# Power.net
KiCad netlist of a schematic drawn in Altium Designer
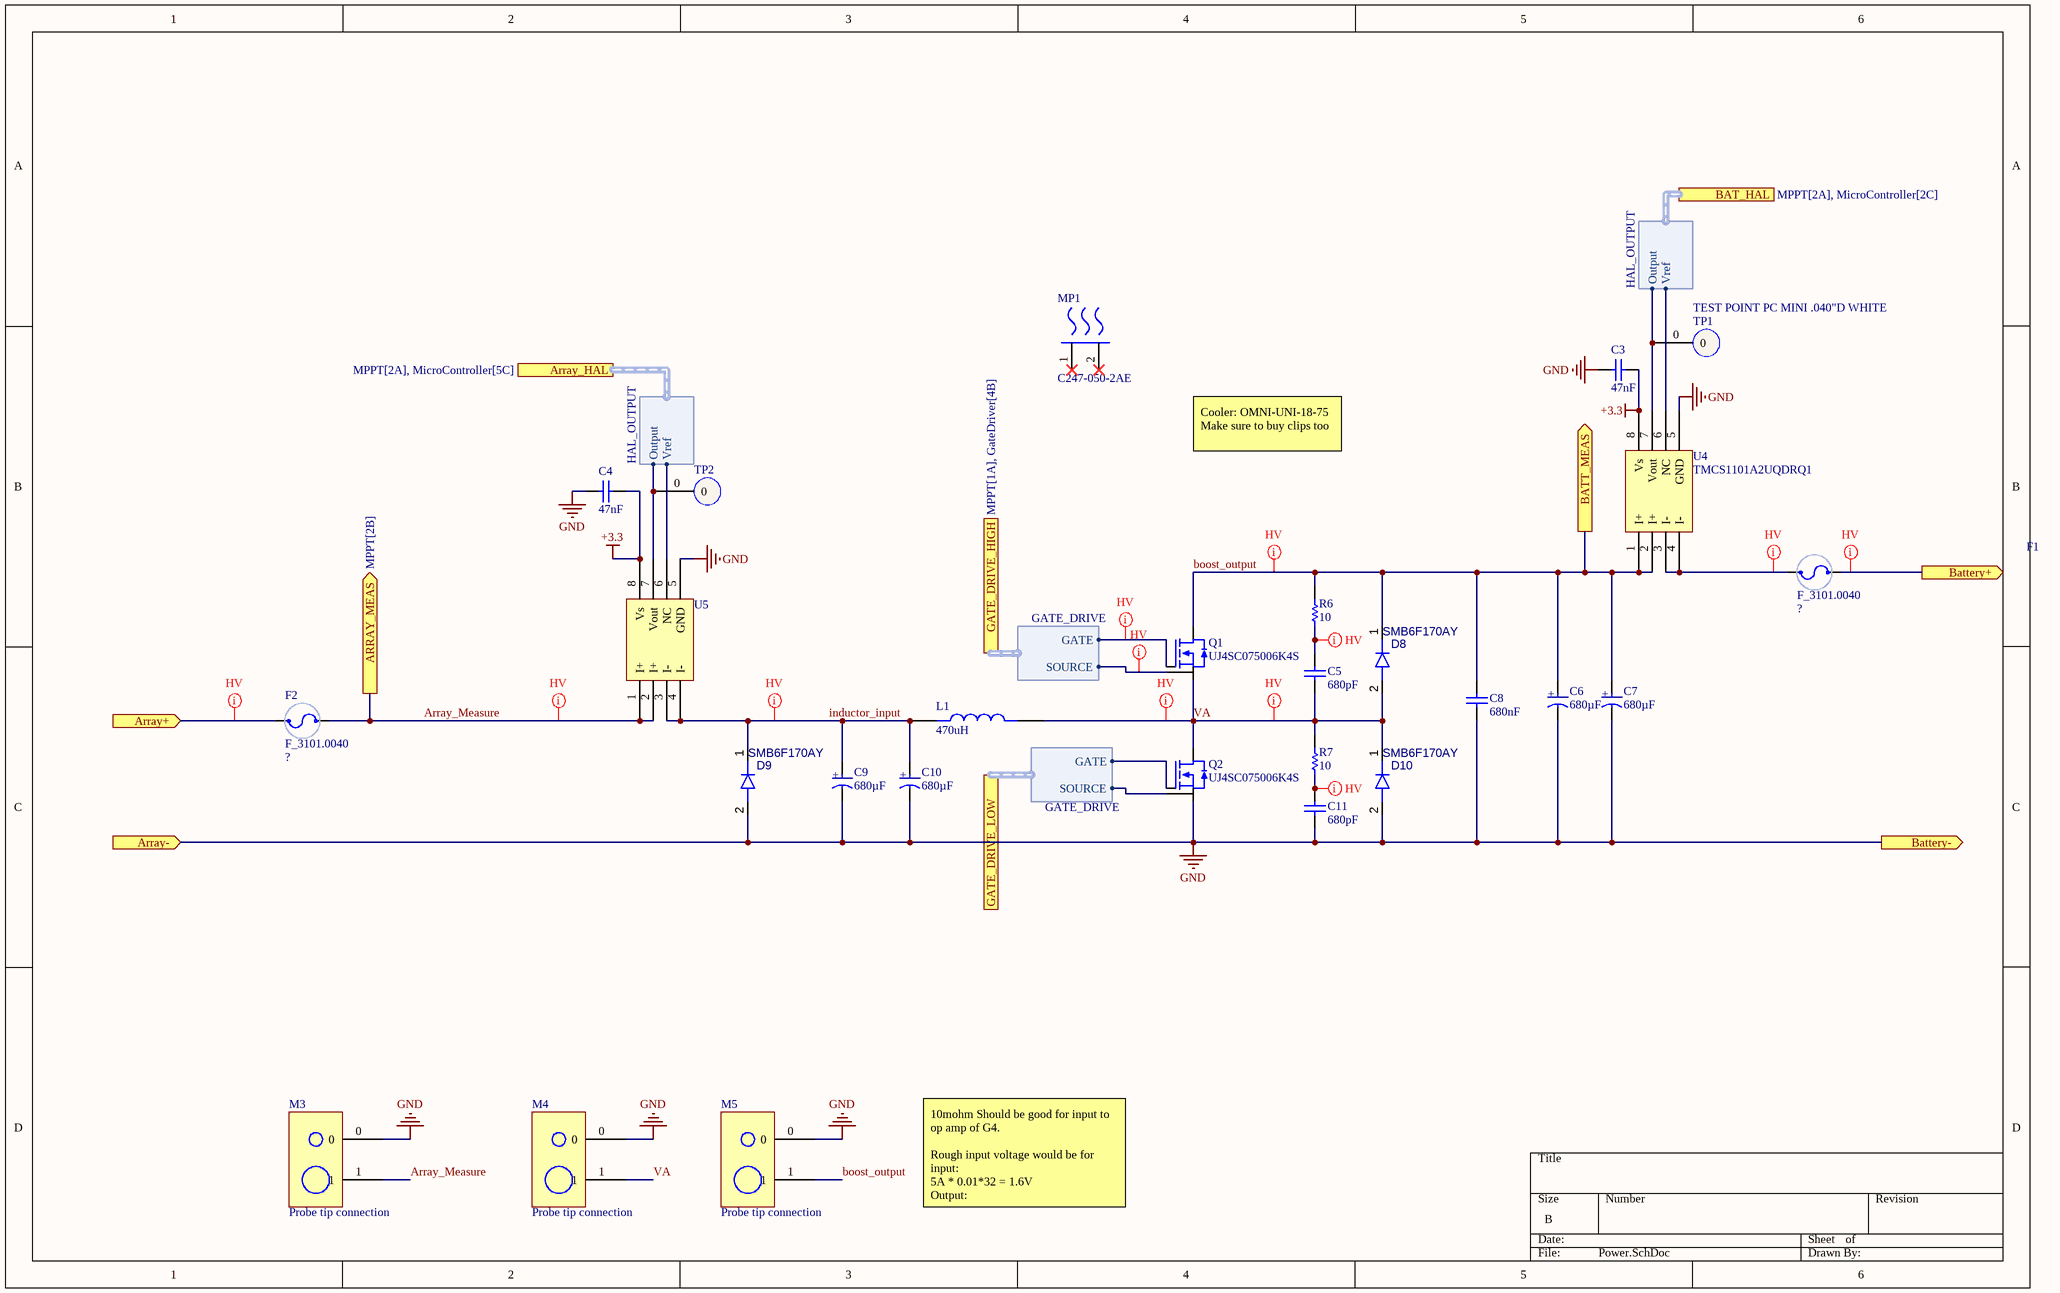
[diagram p0: Power.SchDoc]

(export (version "E")
  (design (tool "Eeschema 10.0.6"))
  (components
    (comp (ref "C3")
      (value "47nF")
      (footprint "0603_CAPACITOR")
      (fields (field (name "TOLERANCE") "10%") (field (name "Comment") "C0603C473K4RECAUTO"))
      (libsource (lib "University of Minnesota - Solar Vehicle Project") (part "Cap"))
    )
    (comp (ref "C4")
      (value "47nF")
      (footprint "0603_CAPACITOR")
      (fields (field (name "TOLERANCE") "10%") (field (name "Comment") "C0603C473K4RECAUTO"))
      (libsource (lib "University of Minnesota - Solar Vehicle Project") (part "Cap"))
    )
    (comp (ref "C5")
      (value "680pF")
      (footprint "0805_Capacitor")
      (fields (field (name "TOLERANCE") "10%") (field (name "Comment") "C0805C681K2RAC7800"))
      (libsource (lib "University of Minnesota - Solar Vehicle Project") (part "Cap"))
    )
    (comp (ref "C6")
      (value "680µF")
      (footprint "381LR681M200J032-Footprint-1")
      (fields (field (name "TOLERANCE") "20%") (field (name "Comment") "381LR681M200K022"))
      (libsource (lib "University of Minnesota - Solar Vehicle Project") (part "C_ALUM"))
    )
    (comp (ref "C7")
      (value "680µF")
      (footprint "381LR681M200J032-Footprint-1")
      (fields (field (name "TOLERANCE") "20%") (field (name "Comment") "381LR681M200K022"))
      (libsource (lib "University of Minnesota - Solar Vehicle Project") (part "C_ALUM"))
    )
    (comp (ref "C8")
      (value "680nF")
      (footprint "684MMR400K-Footprint-1")
      (description "Film Capacitor, Polyester, 400V, 10% +Tol, 10% -Tol, 0.68uF, Through Hole Mount")
      (fields (field (name "TOLERANCE") "10%") (field (name "Comment") "684MMR400K"))
      (libsource (lib "University of Minnesota - Solar Vehicle Project") (part "Cap"))
    )
    (comp (ref "C9")
      (value "680µF")
      (footprint "381LR681M200J032-Footprint-1")
      (fields (field (name "TOLERANCE") "20%") (field (name "Comment") "381LR681M200K022"))
      (libsource (lib "University of Minnesota - Solar Vehicle Project") (part "C_ALUM"))
    )
    (comp (ref "C10")
      (value "680µF")
      (footprint "381LR681M200J032-Footprint-1")
      (fields (field (name "TOLERANCE") "20%") (field (name "Comment") "381LR681M200K022"))
      (libsource (lib "University of Minnesota - Solar Vehicle Project") (part "C_ALUM"))
    )
    (comp (ref "C11")
      (value "680pF")
      (footprint "0805_Capacitor")
      (fields (field (name "TOLERANCE") "10%") (field (name "Comment") "C0805C681K2RAC7800"))
      (libsource (lib "University of Minnesota - Solar Vehicle Project") (part "Cap"))
    )
    (comp (ref "D8")
      (value "SMB6F170AY")
      (footprint "SMB6F170AY-Footprint-1")
      (description "TVS Diodes / ESD Suppressors Automotive 600 W, 170 V TVS in SMB Flat")
      (libsource (lib "University of Minnesota - Solar Vehicle Project") (part "DIODE-2"))
    )
    (comp (ref "D9")
      (value "SMB6F170AY")
      (footprint "SMB6F170AY-Footprint-1")
      (description "TVS Diodes / ESD Suppressors Automotive 600 W, 170 V TVS in SMB Flat")
      (libsource (lib "University of Minnesota - Solar Vehicle Project") (part "DIODE-2"))
    )
    (comp (ref "D10")
      (value "SMB6F170AY")
      (footprint "SMB6F170AY-Footprint-1")
      (description "TVS Diodes / ESD Suppressors Automotive 600 W, 170 V TVS in SMB Flat")
      (libsource (lib "University of Minnesota - Solar Vehicle Project") (part "DIODE-2"))
    )
    (comp (ref "F1")
      (value "F_3101.0040")
      (footprint "F_FPG4")
      (description "Fuse Holder 16A 500V 1 Circuit Cartridge PCB")
      (fields
        (field (name "ALTIUM_VALUE") "?")
        (field (name "MANUFACTURER PART NUMBER") "3101.0040")
        (field (name "MANUFACTURER") "Schurter")
      )
      (libsource (lib "University of Minnesota - Solar Vehicle Project") (part "F_3101.0040"))
    )
    (comp (ref "F2")
      (value "F_3101.0040")
      (footprint "F_FPG4")
      (description "Fuse Holder 16A 500V 1 Circuit Cartridge PCB")
      (fields
        (field (name "ALTIUM_VALUE") "?")
        (field (name "MANUFACTURER PART NUMBER") "3101.0040")
        (field (name "MANUFACTURER") "Schurter")
      )
      (libsource (lib "University of Minnesota - Solar Vehicle Project") (part "F_3101.0040"))
    )
    (comp (ref "L1")
      (value "470uH")
      (footprint "ATCA-08-471M-H-Footprint-1")
      (description "Coustom wound inductor using 79617A7 core")
      (fields (field (name "TOLERANCE") "20%") (field (name "Comment") "ATCA-08-471M-H"))
      (libsource (lib "University of Minnesota - Solar Vehicle Project") (part "ATCA-08-471M-H"))
    )
    (comp (ref "M3")
      (value "Probe tip connection")
      (footprint "Probe tip connection-Footprint-1")
      (description "Connection for oscilscope ground tip")
      (libsource (lib "University of Minnesota - Solar Vehicle Project") (part "Probe tip connection-Symbol-1"))
    )
    (comp (ref "M4")
      (value "Probe tip connection")
      (footprint "Probe tip connection-Footprint-1")
      (description "Connection for oscilscope ground tip")
      (libsource (lib "University of Minnesota - Solar Vehicle Project") (part "Probe tip connection-Symbol-1"))
    )
    (comp (ref "M5")
      (value "Probe tip connection")
      (footprint "Probe tip connection-Footprint-1")
      (description "Connection for oscilscope ground tip")
      (libsource (lib "University of Minnesota - Solar Vehicle Project") (part "Probe tip connection-Symbol-1"))
    )
    (comp (ref "MP1")
      (value "C247-050-2AE")
      (footprint "FP-C247-050-2AE-MFG")
      (description "Heat Sink 2 TO-247 components")
      (libsource (lib "University of Minnesota - Solar Vehicle Project") (part "aa053631d160a0edfc04875c0d6cfd9"))
    )
    (comp (ref "Q1")
      (value "UJ4SC075006K4S")
      (footprint "T_TO_247_4L_UNITEDSIC - Vertical")
      (description "750V/6MOHM, Sic, Stacked Cascode")
      (fields (field (name "MANUFACTURER PART NUMBER") "UF3SC065007K4S"))
      (libsource (lib "University of Minnesota - Solar Vehicle Project") (part "UJ4SC075006K4S"))
    )
    (comp (ref "Q2")
      (value "UJ4SC075006K4S")
      (footprint "T_TO_247_4L_UNITEDSIC - Vertical")
      (description "750V/6MOHM, Sic, Stacked Cascode")
      (fields (field (name "MANUFACTURER PART NUMBER") "UF3SC065007K4S"))
      (libsource (lib "University of Minnesota - Solar Vehicle Project") (part "UJ4SC075006K4S"))
    )
    (comp (ref "R6")
      (value "10")
      (footprint "1210_Resistor")
      (description "Res Thick Film 1210 10 Ohm 1% 1/3W ±100ppm/°C Molded SMD SMD Plastic T/R")
      (fields (field (name "TOLERANCE") "1%") (field (name "POWER") "0.5W"))
      (libsource (lib "University of Minnesota - Solar Vehicle Project") (part "RES-2"))
    )
    (comp (ref "R7")
      (value "10")
      (footprint "1210_Resistor")
      (description "Res Thick Film 1210 10 Ohm 1% 1/3W ±100ppm/°C Molded SMD SMD Plastic T/R")
      (fields (field (name "TOLERANCE") "1%") (field (name "POWER") "0.5W"))
      (libsource (lib "University of Minnesota - Solar Vehicle Project") (part "RES-2"))
    )
    (comp (ref "TP1")
      (value "TEST POINT PC MINI .040\"D WHITE")
      (footprint "TEST POINT 0.040\" WHITE")
      (libsource (lib "University of Minnesota - Solar Vehicle Project") (part "TEST POINT PC MINI .040{dblquote}D WHITE"))
    )
    (comp (ref "TP2")
      (value "TEST POINT PC MINI .040\"D WHITE")
      (footprint "TEST POINT 0.040\" WHITE")
      (libsource (lib "University of Minnesota - Solar Vehicle Project") (part "TEST POINT PC MINI .040{dblquote}D WHITE"))
    )
    (comp (ref "U4")
      (value "TMCS1101A2UQDRQ1")
      (footprint "SOIC127P610X173-8N")
      (description "Automotive, precision isolated current sensor with internal reference 8-SOIC -40 to 125")
      (libsource (lib "University of Minnesota - Solar Vehicle Project") (part "TMCS1101A2UQDRQ1"))
    )
    (comp (ref "U5")
      (value "TMCS1101A2UQDRQ1")
      (footprint "SOIC127P610X173-8N")
      (description "Automotive, precision isolated current sensor with internal reference 8-SOIC -40 to 125")
      (libsource (lib "University of Minnesota - Solar Vehicle Project") (part "TMCS1101A2UQDRQ1"))
    )
  )
  (nets
    (net (code "3") (name "+3.3") (class "Default")
      (node (ref "C3") (pin "2") (pinfunction "2_2") (pintype "passive"))
      (node (ref "C4") (pin "2") (pinfunction "2_2") (pintype "passive"))
      (node (ref "U4") (pin "8") (pinfunction "Vs_8") (pintype "passive"))
      (node (ref "U5") (pin "8") (pinfunction "Vs_8") (pintype "passive"))
    )
    (net (code "4") (name "/Array+") (class "Default")
      (node (ref "F2") (pin "1") (pinfunction "1_1") (pintype "passive"))
    )
    (net (code "5") (name "/Array_Measure") (class "Default")
      (node (ref "F2") (pin "2") (pinfunction "2_2") (pintype "passive"))
      (node (ref "M3") (pin "1") (pinfunction "1_1") (pintype "passive"))
      (node (ref "U5") (pin "1") (pinfunction "I+_1") (pintype "passive"))
      (node (ref "U5") (pin "2") (pinfunction "I+_2") (pintype "passive"))
    )
    (net (code "6") (name "/Battery+") (class "Default")
      (node (ref "F1") (pin "2") (pinfunction "2_2") (pintype "passive"))
    )
    (net (code "7") (name "/VA") (class "Default")
      (node (ref "C5") (pin "1") (pinfunction "1_1") (pintype "passive"))
      (node (ref "D10") (pin "1") (pinfunction "K_1") (pintype "passive"))
      (node (ref "D8") (pin "2") (pinfunction "A_2") (pintype "passive"))
      (node (ref "L1") (pin "2") (pinfunction "2_2") (pintype "passive"))
      (node (ref "M4") (pin "1") (pinfunction "1_1") (pintype "passive"))
      (node (ref "Q1") (pin "2") (pinfunction "S_2") (pintype "passive"))
      (node (ref "Q2") (pin "1") (pinfunction "D_1") (pintype "passive"))
      (node (ref "R7") (pin "2") (pinfunction "2_2") (pintype "passive"))
    )
    (net (code "8") (name "/boost_output") (class "Default")
      (node (ref "C6") (pin "2") (pinfunction "2_2") (pintype "passive"))
      (node (ref "C7") (pin "2") (pinfunction "2_2") (pintype "passive"))
      (node (ref "C8") (pin "2") (pinfunction "2_2") (pintype "passive"))
      (node (ref "D8") (pin "1") (pinfunction "K_1") (pintype "passive"))
      (node (ref "M5") (pin "1") (pinfunction "1_1") (pintype "passive"))
      (node (ref "Q1") (pin "1") (pinfunction "D_1") (pintype "passive"))
      (node (ref "R6") (pin "2") (pinfunction "2_2") (pintype "passive"))
      (node (ref "U4") (pin "1") (pinfunction "I+_1") (pintype "passive"))
      (node (ref "U4") (pin "2") (pinfunction "I+_2") (pintype "passive"))
    )
    (net (code "9") (name "/inductor_input") (class "Default")
      (node (ref "C10") (pin "2") (pinfunction "2_2") (pintype "passive"))
      (node (ref "C9") (pin "2") (pinfunction "2_2") (pintype "passive"))
      (node (ref "D9") (pin "1") (pinfunction "K_1") (pintype "passive"))
      (node (ref "L1") (pin "1") (pinfunction "1_1") (pintype "passive"))
      (node (ref "U5") (pin "3") (pinfunction "I-_3") (pintype "passive"))
      (node (ref "U5") (pin "4") (pinfunction "I-_4") (pintype "passive"))
    )
    (net (code "12") (name "GND") (class "Default")
      (node (ref "C10") (pin "1") (pinfunction "1_1") (pintype "passive"))
      (node (ref "C11") (pin "1") (pinfunction "1_1") (pintype "passive"))
      (node (ref "C3") (pin "1") (pinfunction "1_1") (pintype "passive"))
      (node (ref "C4") (pin "1") (pinfunction "1_1") (pintype "passive"))
      (node (ref "C6") (pin "1") (pinfunction "1_1") (pintype "passive"))
      (node (ref "C7") (pin "1") (pinfunction "1_1") (pintype "passive"))
      (node (ref "C8") (pin "1") (pinfunction "1_1") (pintype "passive"))
      (node (ref "C9") (pin "1") (pinfunction "1_1") (pintype "passive"))
      (node (ref "D10") (pin "2") (pinfunction "A_2") (pintype "passive"))
      (node (ref "D9") (pin "2") (pinfunction "A_2") (pintype "passive"))
      (node (ref "M3") (pin "0") (pinfunction "0_0") (pintype "passive"))
      (node (ref "M4") (pin "0") (pinfunction "0_0") (pintype "passive"))
      (node (ref "M5") (pin "0") (pinfunction "0_0") (pintype "passive"))
      (node (ref "Q2") (pin "2") (pinfunction "S_2") (pintype "passive"))
      (node (ref "U4") (pin "5") (pinfunction "GND_5") (pintype "passive"))
      (node (ref "U5") (pin "5") (pinfunction "GND_5") (pintype "passive"))
    )
    (net (code "13") (name "Net-(C5-Pad2)") (class "Default")
      (node (ref "C5") (pin "2") (pinfunction "2_2") (pintype "passive"))
      (node (ref "R6") (pin "1") (pinfunction "1_1") (pintype "passive"))
    )
    (net (code "14") (name "Net-(C11-Pad2)") (class "Default")
      (node (ref "C11") (pin "2") (pinfunction "2_2") (pintype "passive"))
      (node (ref "R7") (pin "1") (pinfunction "1_1") (pintype "passive"))
    )
    (net (code "15") (name "Net-(F1-Pad1)") (class "Default")
      (node (ref "F1") (pin "1") (pinfunction "1_1") (pintype "passive"))
      (node (ref "U4") (pin "3") (pinfunction "I-_3") (pintype "passive"))
      (node (ref "U4") (pin "4") (pinfunction "I-_4") (pintype "passive"))
    )
    (net (code "16") (name "Net-(U4-Vout)") (class "Default")
      (node (ref "TP1") (pin "0") (pinfunction "0_0") (pintype "passive"))
      (node (ref "U4") (pin "7") (pinfunction "Vout_7") (pintype "passive"))
    )
    (net (code "17") (name "Net-(U5-Vout)") (class "Default")
      (node (ref "TP2") (pin "0") (pinfunction "0_0") (pintype "passive"))
      (node (ref "U5") (pin "7") (pinfunction "Vout_7") (pintype "passive"))
    )
    (net (code "18") (name "unconnected-(MP1-MNT_1-Pad1)") (class "Default")
      (node (ref "MP1") (pin "1") (pinfunction "MNT_1_1") (pintype "passive+no_connect"))
    )
    (net (code "19") (name "unconnected-(MP1-MNT_2-Pad2)") (class "Default")
      (node (ref "MP1") (pin "2") (pinfunction "MNT_2_2") (pintype "passive+no_connect"))
    )
    (net (code "20") (name "unconnected-(Q1-G-Pad4)") (class "Default")
      (node (ref "Q1") (pin "4") (pinfunction "G_4") (pintype "passive"))
    )
    (net (code "21") (name "unconnected-(Q1-K-Pad3)") (class "Default")
      (node (ref "Q1") (pin "3") (pinfunction "K_3") (pintype "passive"))
    )
    (net (code "22") (name "unconnected-(Q2-G-Pad4)") (class "Default")
      (node (ref "Q2") (pin "4") (pinfunction "G_4") (pintype "passive"))
    )
    (net (code "23") (name "unconnected-(Q2-K-Pad3)") (class "Default")
      (node (ref "Q2") (pin "3") (pinfunction "K_3") (pintype "passive"))
    )
    (net (code "24") (name "unconnected-(U4-NC-Pad6)") (class "Default")
      (node (ref "U4") (pin "6") (pinfunction "NC_6") (pintype "passive"))
    )
    (net (code "25") (name "unconnected-(U5-NC-Pad6)") (class "Default")
      (node (ref "U5") (pin "6") (pinfunction "NC_6") (pintype "passive"))
    )
  )
)
